# Module_Connector.net
KiCad netlist of a schematic drawn in Altium Designer
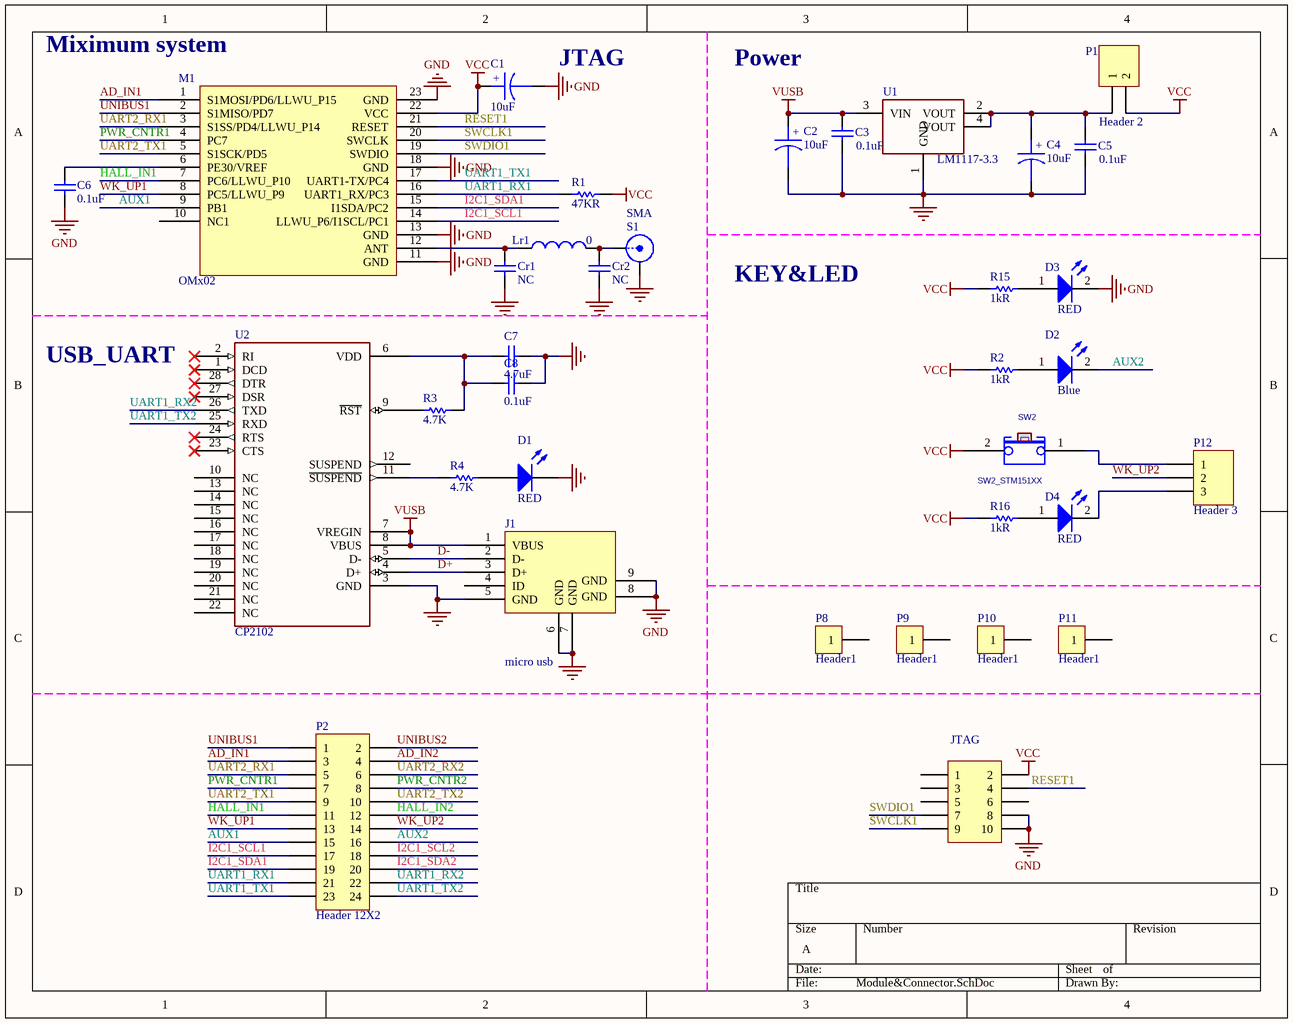
[diagram p0: Module&Connector.SchDoc]

(export (version "E")
  (design (tool "Eeschema 10.0.6"))
  (components
    (comp (ref "C1")
      (value "10uF")
      (footprint "0805")
      (description "Capacitor")
      (libsource (lib "*") (part "CAPACITOR POL"))
    )
    (comp (ref "C2")
      (value "10uF")
      (footprint "0805")
      (description "Capacitor")
      (libsource (lib "*") (part "CAPACITOR POL"))
    )
    (comp (ref "C3")
      (value "0.1uF")
      (footprint "0603RF")
      (description "Capacitor")
      (fields (field (name "PUBLISHER") "Altium Limited"))
      (libsource (lib "*") (part "Cap"))
    )
    (comp (ref "C4")
      (value "10uF")
      (footprint "0805")
      (description "Capacitor")
      (libsource (lib "*") (part "CAPACITOR POL"))
    )
    (comp (ref "C5")
      (value "0.1uF")
      (footprint "0603RF")
      (description "Capacitor")
      (fields (field (name "PUBLISHER") "Altium Limited"))
      (libsource (lib "*") (part "Cap"))
    )
    (comp (ref "C6")
      (value "0.1uF")
      (footprint "0603RF")
      (description "Capacitor (Semiconductor SIM Model)")
      (fields (field (name "PUBLISHER") "Altium Limited"))
      (libsource (lib "Miscellaneous Devices") (part "Cap Semi"))
    )
    (comp (ref "C7")
      (value "4.7uF")
      (footprint "0603RF")
      (description "Capacitor (Semiconductor SIM Model)")
      (fields (field (name "PUBLISHER") "Altium Limited"))
      (libsource (lib "Miscellaneous Devices") (part "Cap Semi"))
    )
    (comp (ref "C8")
      (value "0.1uF")
      (footprint "0603RF")
      (description "Capacitor (Semiconductor SIM Model)")
      (fields (field (name "PUBLISHER") "Altium Limited"))
      (libsource (lib "Miscellaneous Devices") (part "Cap Semi"))
    )
    (comp (ref "Cr1")
      (value "NC")
      (footprint "0603RF")
      (description "Capacitor (Semiconductor SIM Model)")
      (fields (field (name "PUBLISHER") "Altium Limited"))
      (libsource (lib "Miscellaneous Devices") (part "Cap Semi"))
    )
    (comp (ref "Cr2")
      (value "NC")
      (footprint "0603RF")
      (description "Capacitor (Semiconductor SIM Model)")
      (fields (field (name "PUBLISHER") "Altium Limited"))
      (libsource (lib "Miscellaneous Devices") (part "Cap Semi"))
    )
    (comp (ref "D1")
      (value "RED")
      (footprint "LED0603")
      (description "Typical RED, GREEN, YELLOW, AMBER GaAs LED")
      (fields (field (name "PUBLISHER") "Altium Limited"))
      (libsource (lib "Miscellaneous Devices") (part "LED2"))
    )
    (comp (ref "D2")
      (value "Blue")
      (footprint "LED0603")
      (description "Typical RED, GREEN, YELLOW, AMBER GaAs LED")
      (fields (field (name "PUBLISHER") "Altium Limited"))
      (libsource (lib "*") (part "LED2"))
    )
    (comp (ref "D3")
      (value "RED")
      (footprint "LED0603")
      (description "Typical RED, GREEN, YELLOW, AMBER GaAs LED")
      (fields (field (name "PUBLISHER") "Altium Limited"))
      (libsource (lib "*") (part "LED2"))
    )
    (comp (ref "D4")
      (value "RED")
      (footprint "LED0603")
      (description "Typical RED, GREEN, YELLOW, AMBER GaAs LED")
      (fields (field (name "PUBLISHER") "Altium Limited"))
      (libsource (lib "*") (part "LED2"))
    )
    (comp (ref "J1")
      (value "micro usb")
      (footprint "MICROUSB-D")
      (description "同GDI401的USB接口一致")
      (libsource (lib "MySCHLIB") (part "micro usb"))
    )
    (comp (ref "JTAG")
      (value "IDC-10")
      (footprint "JTAG10-MINI")
      (description "双排插针2.54mm")
      (fields (field (name "PUBLISHER") "Altium Limited"))
      (libsource (lib "Miscellaneous Connectors") (part "Header 5X2"))
    )
    (comp (ref "Lr1")
      (value "0")
      (footprint "0603RF")
      (description "Inductor")
      (fields (field (name "PUBLISHER") "Altium Limited"))
      (libsource (lib "Miscellaneous Devices") (part "Inductor"))
    )
    (comp (ref "M1") (value "OMx02") (footprint "OMx02") (libsource (lib "MySCHLIB") (part "OMx02")))
    (comp (ref "P1")
      (value "Header 2")
      (footprint "HDR1X2")
      (description "Header, 2-Pin")
      (fields (field (name "PUBLISHER") "Altium Limited"))
      (libsource (lib "Miscellaneous Connectors") (part "Header 2"))
    )
    (comp (ref "P2")
      (value "Header 12X2")
      (footprint "Header2X12")
      (description "Header, 12-Pin, Dual row")
      (fields (field (name "PUBLISHER") "Altium Limited"))
      (libsource (lib "Miscellaneous Connectors") (part "Header 12X2"))
    )
    (comp (ref "P8") (value "Header1") (footprint "Fix_Hole") (libsource (lib "MySCHLIB") (part "Header1")))
    (comp (ref "P9") (value "Header1") (footprint "Fix_Hole") (libsource (lib "MySCHLIB") (part "Header1")))
    (comp (ref "P10") (value "Header1") (footprint "Fix_Hole") (libsource (lib "MySCHLIB") (part "Header1")))
    (comp (ref "P11") (value "Header1") (footprint "Fix_Hole") (libsource (lib "MySCHLIB") (part "Header1")))
    (comp (ref "P12")
      (value "Header 3")
      (footprint "HDR1X3")
      (description "Header, 3-Pin")
      (fields (field (name "PUBLISHER") "Altium Limited"))
      (libsource (lib "Miscellaneous Connectors") (part "Header 3"))
    )
    (comp (ref "R1")
      (value "47KR")
      (footprint "0603RF")
      (description "Semiconductor Resistor")
      (fields (field (name "PUBLISHER") "Altium Limited"))
      (libsource (lib "Miscellaneous Devices") (part "Res Semi"))
    )
    (comp (ref "R2")
      (value "1kR")
      (footprint "0603RF")
      (description "Semiconductor Resistor")
      (fields (field (name "PUBLISHER") "Altium Limited"))
      (libsource (lib "Miscellaneous Devices") (part "Res Semi"))
    )
    (comp (ref "R3")
      (value "4.7K")
      (footprint "0603RF")
      (description "Semiconductor Resistor")
      (fields (field (name "PUBLISHER") "Altium Limited"))
      (libsource (lib "Miscellaneous Devices") (part "Res Semi"))
    )
    (comp (ref "R4")
      (value "4.7K")
      (footprint "0603RF")
      (description "Semiconductor Resistor")
      (fields (field (name "PUBLISHER") "Altium Limited"))
      (libsource (lib "Miscellaneous Devices") (part "Res Semi"))
    )
    (comp (ref "R15")
      (value "1kR")
      (footprint "0603RF")
      (description "Semiconductor Resistor")
      (fields (field (name "PUBLISHER") "Altium Limited"))
      (libsource (lib "Miscellaneous Devices") (part "Res Semi"))
    )
    (comp (ref "R16")
      (value "1kR")
      (footprint "0603RF")
      (description "Semiconductor Resistor")
      (fields (field (name "PUBLISHER") "Altium Limited"))
      (libsource (lib "Miscellaneous Devices") (part "Res Semi"))
    )
    (comp (ref "S1")
      (value "SMA")
      (footprint "SMA")
      (description "SMB Straight Connector")
      (fields (field (name "PUBLISHER") "Altium Limited"))
      (libsource (lib "Miscellaneous Connectors") (part "SMB"))
    )
    (comp (ref "SW2")
      (value "SW2_STM151XX")
      (description "轻触开关3x4x2,http://www.szlcsc.com/product/details_27383.html")
      (libsource (lib "*") (part "SW2_STM151XX"))
    )
    (comp (ref "U1")
      (value "LM1117-3.3")
      (footprint "SOT-223")
      (description "LM1117 5V转3.3V电源芯片")
      (libsource (lib "NARI") (part "LM1117"))
    )
    (comp (ref "U2")
      (value "CP2102")
      (footprint "QFN28_CP2102")
      (description "USB转UART芯片")
      (libsource (lib "NARI") (part "CP2102"))
    )
  )
  (nets
    (net (code "1") (name "/AD_IN1") (class "Default")
      (node (ref "M1") (pin "1") (pinfunction "S1MOSI/PD6/LLWU_P15_1") (pintype "passive"))
      (node (ref "P2") (pin "3") (pinfunction "3_3") (pintype "passive"))
    )
    (net (code "2") (name "/AD_IN2") (class "Default")
      (node (ref "P2") (pin "4") (pinfunction "4_4") (pintype "passive"))
    )
    (net (code "3") (name "/AUX1") (class "Default")
      (node (ref "M1") (pin "9") (pinfunction "PB1_9") (pintype "passive"))
      (node (ref "P2") (pin "15") (pinfunction "15_15") (pintype "passive"))
    )
    (net (code "4") (name "/AUX2") (class "Default")
      (node (ref "D2") (pin "2") (pinfunction "K_2") (pintype "passive"))
      (node (ref "P2") (pin "16") (pinfunction "16_16") (pintype "passive"))
    )
    (net (code "5") (name "/D+") (class "Default")
      (node (ref "J1") (pin "3") (pinfunction "D+_3") (pintype "passive"))
      (node (ref "U2") (pin "4") (pinfunction "D+_4") (pintype "bidirectional"))
    )
    (net (code "6") (name "/D-") (class "Default")
      (node (ref "J1") (pin "2") (pinfunction "D-_2") (pintype "passive"))
      (node (ref "U2") (pin "5") (pinfunction "D-_5") (pintype "bidirectional"))
    )
    (net (code "7") (name "/HALL_IN1") (class "Default")
      (node (ref "M1") (pin "7") (pinfunction "PC6/LLWU_P10_7") (pintype "passive"))
      (node (ref "P2") (pin "11") (pinfunction "11_11") (pintype "passive"))
    )
    (net (code "8") (name "/HALL_IN2") (class "Default")
      (node (ref "P2") (pin "12") (pinfunction "12_12") (pintype "passive"))
    )
    (net (code "9") (name "/I2C1_SCL1") (class "Default")
      (node (ref "M1") (pin "14") (pinfunction "LLWU_P6/I1SCL/PC1_14") (pintype "passive"))
      (node (ref "P2") (pin "17") (pinfunction "17_17") (pintype "passive"))
    )
    (net (code "10") (name "/I2C1_SCL2") (class "Default")
      (node (ref "P2") (pin "18") (pinfunction "18_18") (pintype "passive"))
    )
    (net (code "11") (name "/I2C1_SDA1") (class "Default")
      (node (ref "M1") (pin "15") (pinfunction "I1SDA/PC2_15") (pintype "passive"))
      (node (ref "P2") (pin "19") (pinfunction "19_19") (pintype "passive"))
    )
    (net (code "12") (name "/I2C1_SDA2") (class "Default")
      (node (ref "P2") (pin "20") (pinfunction "20_20") (pintype "passive"))
    )
    (net (code "13") (name "/PWR_CNTR1") (class "Default")
      (node (ref "M1") (pin "4") (pinfunction "PC7_4") (pintype "passive"))
      (node (ref "P2") (pin "7") (pinfunction "7_7") (pintype "passive"))
    )
    (net (code "14") (name "/PWR_CNTR2") (class "Default")
      (node (ref "P2") (pin "8") (pinfunction "8_8") (pintype "passive"))
    )
    (net (code "15") (name "/RESET1") (class "Default")
      (node (ref "JTAG") (pin "4") (pinfunction "4_4") (pintype "passive"))
      (node (ref "M1") (pin "21") (pinfunction "RESET_21") (pintype "passive"))
    )
    (net (code "16") (name "/SWCLK1") (class "Default")
      (node (ref "JTAG") (pin "9") (pinfunction "9_9") (pintype "passive"))
      (node (ref "M1") (pin "20") (pinfunction "SWCLK_20") (pintype "passive"))
    )
    (net (code "17") (name "/SWDIO1") (class "Default")
      (node (ref "JTAG") (pin "7") (pinfunction "7_7") (pintype "passive"))
      (node (ref "M1") (pin "19") (pinfunction "SWDIO_19") (pintype "passive"))
    )
    (net (code "18") (name "/UART1_RX1") (class "Default")
      (node (ref "M1") (pin "16") (pinfunction "UART1_RX/PC3_16") (pintype "passive"))
      (node (ref "P2") (pin "21") (pinfunction "21_21") (pintype "passive"))
      (node (ref "R1") (pin "1") (pinfunction "1_1") (pintype "passive"))
    )
    (net (code "19") (name "/UART1_RX2") (class "Default")
      (node (ref "P2") (pin "22") (pinfunction "22_22") (pintype "passive"))
      (node (ref "U2") (pin "26") (pinfunction "TXD_26") (pintype "output"))
    )
    (net (code "20") (name "/UART1_TX1") (class "Default")
      (node (ref "M1") (pin "17") (pinfunction "UART1-TX/PC4_17") (pintype "passive"))
      (node (ref "P2") (pin "23") (pinfunction "23_23") (pintype "passive"))
    )
    (net (code "21") (name "/UART1_TX2") (class "Default")
      (node (ref "P2") (pin "24") (pinfunction "24_24") (pintype "passive"))
      (node (ref "U2") (pin "25") (pinfunction "RXD_25") (pintype "input"))
    )
    (net (code "22") (name "/UART2_RX1") (class "Default")
      (node (ref "M1") (pin "3") (pinfunction "S1SS/PD4/LLWU_P14_3") (pintype "passive"))
      (node (ref "P2") (pin "5") (pinfunction "5_5") (pintype "passive"))
    )
    (net (code "23") (name "/UART2_RX2") (class "Default")
      (node (ref "P2") (pin "6") (pinfunction "6_6") (pintype "passive"))
    )
    (net (code "24") (name "/UART2_TX1") (class "Default")
      (node (ref "M1") (pin "5") (pinfunction "S1SCK/PD5_5") (pintype "passive"))
      (node (ref "P2") (pin "9") (pinfunction "9_9") (pintype "passive"))
    )
    (net (code "25") (name "/UART2_TX2") (class "Default")
      (node (ref "P2") (pin "10") (pinfunction "10_10") (pintype "passive"))
    )
    (net (code "26") (name "/UNIBUS1") (class "Default")
      (node (ref "M1") (pin "2") (pinfunction "S1MISO/PD7_2") (pintype "passive"))
      (node (ref "P2") (pin "1") (pinfunction "1_1") (pintype "passive"))
    )
    (net (code "27") (name "/UNIBUS2") (class "Default")
      (node (ref "P2") (pin "2") (pinfunction "2_2") (pintype "passive"))
    )
    (net (code "28") (name "/WK_UP1") (class "Default")
      (node (ref "M1") (pin "8") (pinfunction "PC5/LLWU_P9_8") (pintype "passive"))
      (node (ref "P2") (pin "13") (pinfunction "13_13") (pintype "passive"))
    )
    (net (code "29") (name "/WK_UP2") (class "Default")
      (node (ref "P12") (pin "2") (pinfunction "2_2") (pintype "passive"))
      (node (ref "P2") (pin "14") (pinfunction "14_14") (pintype "passive"))
    )
    (net (code "30") (name "GND") (class "Default")
      (node (ref "C1") (pin "2") (pinfunction "2_2") (pintype "passive"))
      (node (ref "C2") (pin "2") (pinfunction "2_2") (pintype "passive"))
      (node (ref "C3") (pin "2") (pinfunction "2_2") (pintype "passive"))
      (node (ref "C4") (pin "2") (pinfunction "2_2") (pintype "passive"))
      (node (ref "C5") (pin "2") (pinfunction "2_2") (pintype "passive"))
      (node (ref "C6") (pin "1") (pinfunction "1_1") (pintype "passive"))
      (node (ref "C7") (pin "2") (pinfunction "2_2") (pintype "passive"))
      (node (ref "C8") (pin "2") (pinfunction "2_2") (pintype "passive"))
      (node (ref "Cr1") (pin "1") (pinfunction "1_1") (pintype "passive"))
      (node (ref "Cr2") (pin "1") (pinfunction "1_1") (pintype "passive"))
      (node (ref "D1") (pin "2") (pinfunction "K_2") (pintype "passive"))
      (node (ref "D3") (pin "2") (pinfunction "K_2") (pintype "passive"))
      (node (ref "J1") (pin "5") (pinfunction "GND_5") (pintype "passive"))
      (node (ref "J1") (pin "6") (pinfunction "GND_6") (pintype "passive"))
      (node (ref "J1") (pin "7") (pinfunction "GND_7") (pintype "passive"))
      (node (ref "J1") (pin "8") (pinfunction "GND_8") (pintype "passive"))
      (node (ref "J1") (pin "9") (pinfunction "GND_9") (pintype "passive"))
      (node (ref "JTAG") (pin "10") (pinfunction "10_10") (pintype "passive"))
      (node (ref "JTAG") (pin "8") (pinfunction "8_8") (pintype "passive"))
      (node (ref "M1") (pin "11") (pinfunction "GND_11") (pintype "passive"))
      (node (ref "M1") (pin "13") (pinfunction "GND_13") (pintype "passive"))
      (node (ref "M1") (pin "18") (pinfunction "GND_18") (pintype "passive"))
      (node (ref "M1") (pin "23") (pinfunction "GND_23") (pintype "passive"))
      (node (ref "S1") (pin "2") (pinfunction "Y_2") (pintype "passive"))
      (node (ref "U1") (pin "1") (pinfunction "GND_1") (pintype "power_in"))
      (node (ref "U2") (pin "0") (pinfunction "GND_0") (pintype "power_in"))
      (node (ref "U2") (pin "3") (pinfunction "GND_3") (pintype "power_in"))
    )
    (net (code "31") (name "Net-(C4-Pad1)") (class "Default")
      (node (ref "C4") (pin "1") (pinfunction "1_1") (pintype "passive"))
      (node (ref "C5") (pin "1") (pinfunction "1_1") (pintype "passive"))
      (node (ref "P1") (pin "1") (pinfunction "1_1") (pintype "passive"))
      (node (ref "U1") (pin "2") (pinfunction "VOUT_2") (pintype "power_in"))
      (node (ref "U1") (pin "4") (pinfunction "VOUT_4") (pintype "power_in"))
    )
    (net (code "32") (name "Net-(D1-A)") (class "Default")
      (node (ref "D1") (pin "1") (pinfunction "A_1") (pintype "passive"))
      (node (ref "R4") (pin "2") (pinfunction "2_2") (pintype "passive"))
    )
    (net (code "33") (name "Net-(D2-A)") (class "Default")
      (node (ref "D2") (pin "1") (pinfunction "A_1") (pintype "passive"))
      (node (ref "R2") (pin "1") (pinfunction "1_1") (pintype "passive"))
    )
    (net (code "34") (name "Net-(D3-A)") (class "Default")
      (node (ref "D3") (pin "1") (pinfunction "A_1") (pintype "passive"))
      (node (ref "R15") (pin "1") (pinfunction "1_1") (pintype "passive"))
    )
    (net (code "35") (name "Net-(D4-A)") (class "Default")
      (node (ref "D4") (pin "1") (pinfunction "A_1") (pintype "passive"))
      (node (ref "R16") (pin "1") (pinfunction "1_1") (pintype "passive"))
    )
    (net (code "36") (name "Net-(D4-K)") (class "Default")
      (node (ref "D4") (pin "2") (pinfunction "K_2") (pintype "passive"))
      (node (ref "P12") (pin "3") (pinfunction "3_3") (pintype "passive"))
    )
    (net (code "37") (name "Net-(M1-ANT)") (class "Default")
      (node (ref "Cr1") (pin "2") (pinfunction "2_2") (pintype "passive"))
      (node (ref "Lr1") (pin "1") (pinfunction "1_1") (pintype "passive"))
      (node (ref "M1") (pin "12") (pinfunction "ANT_12") (pintype "passive"))
    )
    (net (code "38") (name "Net-(M1-PE30{slash}VREF)") (class "Default")
      (node (ref "C6") (pin "2") (pinfunction "2_2") (pintype "passive"))
      (node (ref "M1") (pin "6") (pinfunction "PE30/VREF_6") (pintype "passive"))
    )
    (net (code "39") (name "Net-(S1-X)") (class "Default")
      (node (ref "Cr2") (pin "2") (pinfunction "2_2") (pintype "passive"))
      (node (ref "Lr1") (pin "2") (pinfunction "2_2") (pintype "passive"))
      (node (ref "S1") (pin "1") (pinfunction "X_1") (pintype "passive"))
    )
    (net (code "40") (name "Net-(SW2-SW1)") (class "Default")
      (node (ref "P12") (pin "1") (pinfunction "1_1") (pintype "passive"))
      (node (ref "SW2") (pin "1") (pinfunction "SW1_1") (pintype "passive"))
    )
    (net (code "41") (name "Net-(U2-VDD)") (class "Default")
      (node (ref "C7") (pin "1") (pinfunction "1_1") (pintype "passive"))
      (node (ref "C8") (pin "1") (pinfunction "1_1") (pintype "passive"))
      (node (ref "R3") (pin "2") (pinfunction "2_2") (pintype "passive"))
      (node (ref "U2") (pin "6") (pinfunction "VDD_6") (pintype "power_in"))
    )
    (net (code "42") (name "Net-(U2-~{RST})") (class "Default")
      (node (ref "R3") (pin "1") (pinfunction "1_1") (pintype "passive"))
      (node (ref "U2") (pin "9") (pinfunction "~{RST}_9") (pintype "bidirectional"))
    )
    (net (code "43") (name "Net-(U2-~{SUSPEND})") (class "Default")
      (node (ref "R4") (pin "1") (pinfunction "1_1") (pintype "passive"))
      (node (ref "U2") (pin "11") (pinfunction "~{SUSPEND}_11") (pintype "output"))
    )
    (net (code "44") (name "VCC") (class "Default")
      (node (ref "C1") (pin "1") (pinfunction "1_1") (pintype "passive"))
      (node (ref "JTAG") (pin "2") (pinfunction "2_2") (pintype "passive"))
      (node (ref "M1") (pin "22") (pinfunction "VCC_22") (pintype "passive"))
      (node (ref "P1") (pin "2") (pinfunction "2_2") (pintype "passive"))
      (node (ref "R1") (pin "2") (pinfunction "2_2") (pintype "passive"))
      (node (ref "R15") (pin "2") (pinfunction "2_2") (pintype "passive"))
      (node (ref "R16") (pin "2") (pinfunction "2_2") (pintype "passive"))
      (node (ref "R2") (pin "2") (pinfunction "2_2") (pintype "passive"))
      (node (ref "SW2") (pin "2") (pinfunction "SW2_2") (pintype "passive"))
    )
    (net (code "45") (name "VUSB") (class "Default")
      (node (ref "C2") (pin "1") (pinfunction "1_1") (pintype "passive"))
      (node (ref "C3") (pin "1") (pinfunction "1_1") (pintype "passive"))
      (node (ref "J1") (pin "1") (pinfunction "VBUS_1") (pintype "passive"))
      (node (ref "U1") (pin "3") (pinfunction "VIN_3") (pintype "power_in"))
      (node (ref "U2") (pin "7") (pinfunction "VREGIN_7") (pintype "power_in"))
      (node (ref "U2") (pin "8") (pinfunction "VBUS_8") (pintype "power_in"))
    )
    (net (code "46") (name "unconnected-(J1-ID-Pad4)") (class "Default")
      (node (ref "J1") (pin "4") (pinfunction "ID_4") (pintype "passive"))
    )
    (net (code "47") (name "unconnected-(JTAG-Pad1)") (class "Default")
      (node (ref "JTAG") (pin "1") (pinfunction "1_1") (pintype "passive"))
    )
    (net (code "48") (name "unconnected-(JTAG-Pad3)") (class "Default")
      (node (ref "JTAG") (pin "3") (pinfunction "3_3") (pintype "passive"))
    )
    (net (code "49") (name "unconnected-(JTAG-Pad5)") (class "Default")
      (node (ref "JTAG") (pin "5") (pinfunction "5_5") (pintype "passive"))
    )
    (net (code "50") (name "unconnected-(JTAG-Pad6)") (class "Default")
      (node (ref "JTAG") (pin "6") (pinfunction "6_6") (pintype "passive"))
    )
    (net (code "51") (name "unconnected-(M1-NC1-Pad10)") (class "Default")
      (node (ref "M1") (pin "10") (pinfunction "NC1_10") (pintype "passive"))
    )
    (net (code "52") (name "unconnected-(P8-Pad1)") (class "Default")
      (node (ref "P8") (pin "1") (pinfunction "1_1") (pintype "passive"))
    )
    (net (code "53") (name "unconnected-(P9-Pad1)") (class "Default")
      (node (ref "P9") (pin "1") (pinfunction "1_1") (pintype "passive"))
    )
    (net (code "54") (name "unconnected-(P10-Pad1)") (class "Default")
      (node (ref "P10") (pin "1") (pinfunction "1_1") (pintype "passive"))
    )
    (net (code "55") (name "unconnected-(P11-Pad1)") (class "Default")
      (node (ref "P11") (pin "1") (pinfunction "1_1") (pintype "passive"))
    )
    (net (code "56") (name "unconnected-(U2-CTS-Pad23)") (class "Default")
      (node (ref "U2") (pin "23") (pinfunction "CTS_23") (pintype "input+no_connect"))
    )
    (net (code "57") (name "unconnected-(U2-DCD-Pad1)") (class "Default")
      (node (ref "U2") (pin "1") (pinfunction "DCD_1") (pintype "input+no_connect"))
    )
    (net (code "58") (name "unconnected-(U2-DSR-Pad27)") (class "Default")
      (node (ref "U2") (pin "27") (pinfunction "DSR_27") (pintype "input+no_connect"))
    )
    (net (code "59") (name "unconnected-(U2-DTR-Pad28)") (class "Default")
      (node (ref "U2") (pin "28") (pinfunction "DTR_28") (pintype "output+no_connect"))
    )
    (net (code "60") (name "unconnected-(U2-NC-Pad10)") (class "Default")
      (node (ref "U2") (pin "10") (pinfunction "NC_10") (pintype "passive"))
    )
    (net (code "61") (name "unconnected-(U2-NC-Pad13)") (class "Default")
      (node (ref "U2") (pin "13") (pinfunction "NC_13") (pintype "passive"))
    )
    (net (code "62") (name "unconnected-(U2-NC-Pad14)") (class "Default")
      (node (ref "U2") (pin "14") (pinfunction "NC_14") (pintype "passive"))
    )
    (net (code "63") (name "unconnected-(U2-NC-Pad15)") (class "Default")
      (node (ref "U2") (pin "15") (pinfunction "NC_15") (pintype "passive"))
    )
    (net (code "64") (name "unconnected-(U2-NC-Pad16)") (class "Default")
      (node (ref "U2") (pin "16") (pinfunction "NC_16") (pintype "passive"))
    )
    (net (code "65") (name "unconnected-(U2-NC-Pad17)") (class "Default")
      (node (ref "U2") (pin "17") (pinfunction "NC_17") (pintype "passive"))
    )
    (net (code "66") (name "unconnected-(U2-NC-Pad18)") (class "Default")
      (node (ref "U2") (pin "18") (pinfunction "NC_18") (pintype "passive"))
    )
    (net (code "67") (name "unconnected-(U2-NC-Pad19)") (class "Default")
      (node (ref "U2") (pin "19") (pinfunction "NC_19") (pintype "passive"))
    )
    (net (code "68") (name "unconnected-(U2-NC-Pad20)") (class "Default")
      (node (ref "U2") (pin "20") (pinfunction "NC_20") (pintype "passive"))
    )
    (net (code "69") (name "unconnected-(U2-NC-Pad21)") (class "Default")
      (node (ref "U2") (pin "21") (pinfunction "NC_21") (pintype "passive"))
    )
    (net (code "70") (name "unconnected-(U2-NC-Pad22)") (class "Default")
      (node (ref "U2") (pin "22") (pinfunction "NC_22") (pintype "passive"))
    )
    (net (code "71") (name "unconnected-(U2-RI-Pad2)") (class "Default")
      (node (ref "U2") (pin "2") (pinfunction "RI_2") (pintype "input+no_connect"))
    )
    (net (code "72") (name "unconnected-(U2-RTS-Pad24)") (class "Default")
      (node (ref "U2") (pin "24") (pinfunction "RTS_24") (pintype "output+no_connect"))
    )
    (net (code "73") (name "unconnected-(U2-SUSPEND-Pad12)") (class "Default")
      (node (ref "U2") (pin "12") (pinfunction "SUSPEND_12") (pintype "output"))
    )
  )
)
